# 51-2001-01-12_04_Power_Module_Schematic.net
KiCad netlist of a schematic drawn in Altium Designer
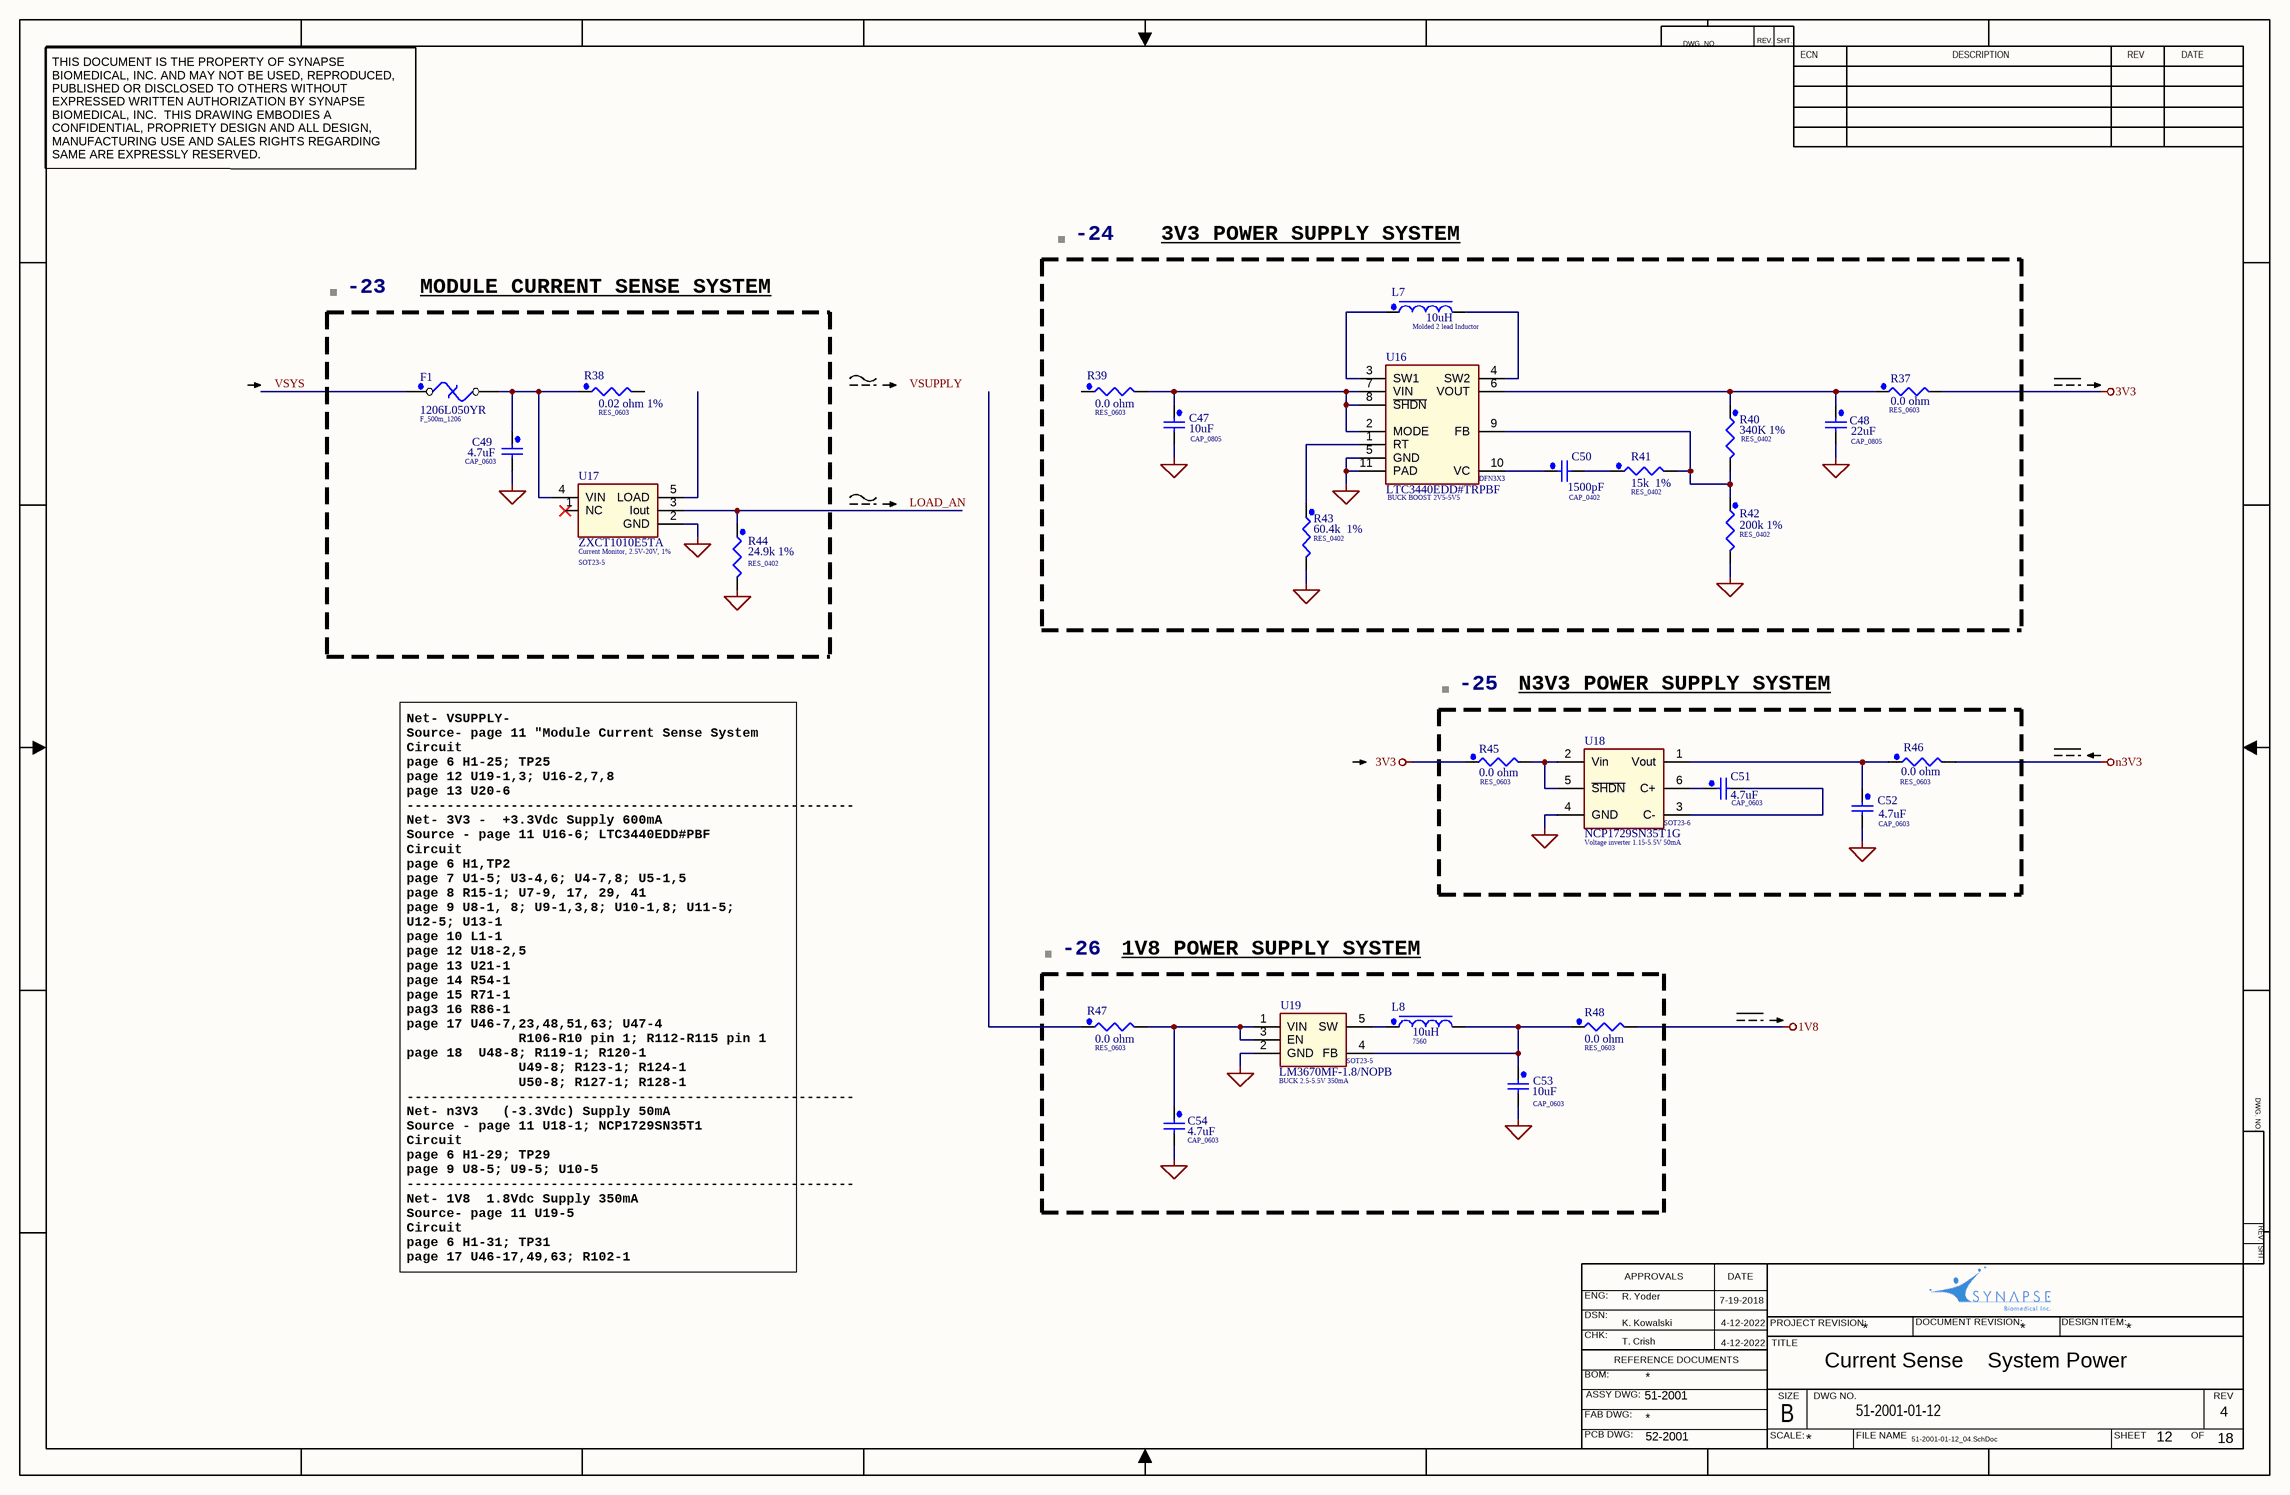
[diagram p0: 51-2001-01-12_04 Power Module Schematic.SchDoc]

(export (version "E")
  (design (tool "Eeschema 10.0.6"))
  (components
    (comp (ref "-23")
      (value "BOM_S1")
      (description "BOM item small graphic")
      (fields (field (name "XDESCRIPTION") "MODULE CURRENT SENSE SYSTEM"))
      (libsource (lib "BOM_sym") (part "BOM_S1"))
    )
    (comp (ref "-24")
      (value "BOM_S1")
      (description "BOM item small graphic")
      (fields (field (name "XDESCRIPTION") "3V3 POWER SUPPLY SYSTEM"))
      (libsource (lib "BOM_sym") (part "BOM_S1"))
    )
    (comp (ref "-25")
      (value "BOM_S1")
      (description "BOM item small graphic")
      (fields (field (name "XDESCRIPTION") "N3V3 POWER SUPPLY SYSTEM"))
      (libsource (lib "BOM_sym") (part "BOM_S1"))
    )
    (comp (ref "-26")
      (value "BOM_S1")
      (description "BOM item small graphic")
      (fields (field (name "XDESCRIPTION") "1V8 POWER SUPPLY SYSTEM"))
      (libsource (lib "BOM_sym") (part "BOM_S1"))
    )
    (comp (ref "C47")
      (value "10uF")
      (footprint "CAP_0805")
      (description "10uF, 16V, X5R, 10%, 0805, RoHS")
      (fields
        (field (name "MFR") "Murata Electronics North America")
        (field (name "PACKAGEDESCRIPTION") "CAP_0805")
        (field (name "MPN") "GRM21BR61C106KE15L")
      )
      (libsource (lib "NNPS Integrated Parts") (part "EMK212BJ106KG-T"))
    )
    (comp (ref "C48")
      (value "22uF")
      (footprint "CAP_0805")
      (description "22uF, 6.3V, X5R, 20%, 0805,RoHS")
      (fields
        (field (name "MFR") "Murata Electronics North America")
        (field (name "PACKAGEDESCRIPTION") "CAP_0805")
        (field (name "MPN") "GRM21BR60J226ME39L")
      )
      (libsource (lib "NNPS Integrated Parts") (part "ECJ-2FB0J226M"))
    )
    (comp (ref "C49")
      (value "4.7uF")
      (footprint "CAP_0603")
      (description "4.7uF, 10V, X5R, 10%, 0603, RoHS")
      (fields
        (field (name "MFR") "Murata Electronics North America")
        (field (name "PACKAGEDESCRIPTION") "CAP_0603")
        (field (name "MPN") "GRM185R61A475KE11D")
      )
      (libsource (lib "NNPS Integrated Parts") (part "LMK107BJ475KA-T"))
    )
    (comp (ref "C50")
      (value "1500pF")
      (footprint "CAP_0402")
      (description "1500pF, 50V, X7R, 10%, 0402, RoHS")
      (fields
        (field (name "MFR") "Murata Electronics North America")
        (field (name "PACKAGEDESCRIPTION") "CAP_0402")
        (field (name "MPN") "GRM155R71H152KA01D")
      )
      (libsource (lib "NNPS Integrated Parts") (part "ECJ-0EB1H152K"))
    )
    (comp (ref "C51")
      (value "4.7uF")
      (footprint "CAP_0603")
      (description "4.7uF, 10V, X5R, 10%, 0603, RoHS")
      (fields
        (field (name "MFR") "Murata Electronics North America")
        (field (name "PACKAGEDESCRIPTION") "CAP_0603")
        (field (name "MPN") "GRM185R61A475KE11D")
      )
      (libsource (lib "NNPS Integrated Parts") (part "LMK107BJ475KA-T"))
    )
    (comp (ref "C52")
      (value "4.7uF")
      (footprint "CAP_0603")
      (description "4.7uF, 10V, X5R, 10%, 0603, RoHS")
      (fields
        (field (name "MFR") "Murata Electronics North America")
        (field (name "PACKAGEDESCRIPTION") "CAP_0603")
        (field (name "MPN") "GRM185R61A475KE11D")
      )
      (libsource (lib "NNPS Integrated Parts") (part "LMK107BJ475KA-T"))
    )
    (comp (ref "C53")
      (value "10uF")
      (footprint "CAP_0603")
      (description "10uF, 6.3V, X5R, 0603_20%, RoHS")
      (fields
        (field (name "MFR") "Murata Electronics North America")
        (field (name "PACKAGEDESCRIPTION") "CAP_0603")
        (field (name "MPN") "GRM188R60J106ME47J")
      )
      (libsource (lib "NNPS Integrated Parts") (part "ECJ-1VB0J106M"))
    )
    (comp (ref "C54")
      (value "4.7uF")
      (footprint "CAP_0603")
      (description "4.7uF, 10V, X5R, 10%, 0603, RoHS")
      (fields
        (field (name "MFR") "Murata Electronics North America")
        (field (name "PACKAGEDESCRIPTION") "CAP_0603")
        (field (name "MPN") "GRM185R61A475KE11D")
      )
      (libsource (lib "NNPS Integrated Parts") (part "LMK107BJ475KA-T"))
    )
    (comp (ref "F1")
      (value "F_500m_1206")
      (footprint "FUSE_1206")
      (description "PTC Resettable, 500mA, 0.4 ohm,  6V, 1206, RoHS")
      (fields
        (field (name "MFR") "Littelfuse")
        (field (name "PACKAGEDESCRIPTION") "F_500m_1206")
        (field (name "MPN") "1206L050YR")
      )
      (libsource (lib "NNPS Integrated Parts") (part "1206L050YR"))
    )
    (comp (ref "L7")
      (value "10uH")
      (footprint "IND-P1166NL")
      (description "10uH, 1.6A, 20%, 3030, RoHS")
      (fields
        (field (name "MFR") "Pulse")
        (field (name "PACKAGEDESCRIPTION") "Molded 2 lead Inductor")
        (field (name "MPN") "P1166.103T")
      )
      (libsource (lib "NNPS Integrated Parts") (part "P1166.103T"))
    )
    (comp (ref "L8")
      (value "10uH")
      (footprint "IND-ELL-6RH")
      (description "10uH, 1.1A, 2626, 20%, RoHS")
      (fields
        (field (name "MFR") "Panasonic")
        (field (name "PACKAGEDESCRIPTION") "7560")
        (field (name "MPN") "ELL6RH100M")
      )
      (libsource (lib "NNPS Integrated Parts") (part "ELL6RH100M"))
    )
    (comp (ref "R37")
      (value "0.0 ohm")
      (footprint "RES_0603")
      (description "0.0 ohm, 1/16W, 0603, RoHS")
      (fields
        (field (name "MFR") "Vishay Dale")
        (field (name "PACKAGEDESCRIPTION") "RES_0603")
        (field (name "MPN") "CRCW06030000Z0EA")
      )
      (libsource (lib "NNPS Integrated Parts") (part "MCR03ERTJ000"))
    )
    (comp (ref "R38")
      (value "0.02 ohm 1%")
      (footprint "RES_0603")
      (description "0.02 ohm, 1%, 1/10W, 0603, RoHS")
      (fields
        (field (name "MFR") "Vishay Dale")
        (field (name "PACKAGEDESCRIPTION") "RES_0603")
        (field (name "MPN") "WSL0603R0200FEA")
      )
      (libsource (lib "NNPS Integrated Parts") (part "WSL0603R0200FEA"))
    )
    (comp (ref "R39")
      (value "0.0 ohm")
      (footprint "RES_0603")
      (description "0.0 ohm, 1/16W, 0603, RoHS")
      (fields
        (field (name "MFR") "Vishay Dale")
        (field (name "PACKAGEDESCRIPTION") "RES_0603")
        (field (name "MPN") "CRCW06030000Z0EA")
      )
      (libsource (lib "NNPS Integrated Parts") (part "MCR03ERTJ000"))
    )
    (comp (ref "R40")
      (value "340K 1%")
      (footprint "RES_0402")
      (description "340k ohm, 1%, 1/16W, 0402, RoHS")
      (fields
        (field (name "MFR") "Vishay Dale")
        (field (name "PACKAGEDESCRIPTION") "RES_0402")
        (field (name "MPN") "CRCW0402340KFKED")
      )
      (libsource (lib "NNPS Integrated Parts") (part "CRCW0402340KFKED"))
    )
    (comp (ref "R41")
      (value "15k  1%")
      (footprint "RES_0402")
      (description "15.0k ohm, 1%, 1/16W, smd, 0402, RoHS")
      (fields
        (field (name "MFR") "Vishay Dale")
        (field (name "PACKAGEDESCRIPTION") "RES_0402")
        (field (name "MPN") "CRCW040215K0FKED")
      )
      (libsource (lib "NNPS Integrated Parts") (part "MCR01MZPF1502"))
    )
    (comp (ref "R42")
      (value "200k 1%")
      (footprint "RES_0402")
      (description "200k ohm, 1%, 1/16W, 0402, RoHS")
      (fields
        (field (name "MFR") "Vishay Dale")
        (field (name "PACKAGEDESCRIPTION") "RES_0402")
        (field (name "MPN") "CRCW0402200KFKED")
      )
      (libsource (lib "NNPS Integrated Parts") (part "MCR01MZPF2003"))
    )
    (comp (ref "R43")
      (value "60.4k  1%")
      (footprint "RES_0402")
      (description "60.4k ohm, 1%, 1/16W, 0402, RoHS")
      (fields
        (field (name "MFR") "Vishay Dale")
        (field (name "PACKAGEDESCRIPTION") "RES_0402")
        (field (name "MPN") "CRCW040260K4FKED")
      )
      (libsource (lib "NNPS Integrated Parts") (part "MCR01MZPF6042"))
    )
    (comp (ref "R44")
      (value "24.9k 1%")
      (footprint "RES_0402")
      (description "24.9k ohm, 1%, 1/16W, 0402, RoHS")
      (fields
        (field (name "MFR") "Vishay Dale")
        (field (name "PACKAGEDESCRIPTION") "RES_0402")
        (field (name "MPN") "CRCW040224K9FKED")
      )
      (libsource (lib "NNPS Integrated Parts") (part "MCR01MZPF2492"))
    )
    (comp (ref "R45")
      (value "0.0 ohm")
      (footprint "RES_0603")
      (description "0.0 ohm, 1/16W, 0603, RoHS")
      (fields
        (field (name "MFR") "Vishay Dale")
        (field (name "PACKAGEDESCRIPTION") "RES_0603")
        (field (name "MPN") "CRCW06030000Z0EA")
      )
      (libsource (lib "NNPS Integrated Parts") (part "MCR03ERTJ000"))
    )
    (comp (ref "R46")
      (value "0.0 ohm")
      (footprint "RES_0603")
      (description "0.0 ohm, 1/16W, 0603, RoHS")
      (fields
        (field (name "MFR") "Vishay Dale")
        (field (name "PACKAGEDESCRIPTION") "RES_0603")
        (field (name "MPN") "CRCW06030000Z0EA")
      )
      (libsource (lib "NNPS Integrated Parts") (part "MCR03ERTJ000"))
    )
    (comp (ref "R47")
      (value "0.0 ohm")
      (footprint "RES_0603")
      (description "0.0 ohm, 1/16W, 0603, RoHS")
      (fields
        (field (name "MFR") "Vishay Dale")
        (field (name "PACKAGEDESCRIPTION") "RES_0603")
        (field (name "MPN") "CRCW06030000Z0EA")
      )
      (libsource (lib "NNPS Integrated Parts") (part "MCR03ERTJ000"))
    )
    (comp (ref "R48")
      (value "0.0 ohm")
      (footprint "RES_0603")
      (description "0.0 ohm, 1/16W, 0603, RoHS")
      (fields
        (field (name "MFR") "Vishay Dale")
        (field (name "PACKAGEDESCRIPTION") "RES_0603")
        (field (name "MPN") "CRCW06030000Z0EA")
      )
      (libsource (lib "NNPS Integrated Parts") (part "MCR03ERTJ000"))
    )
    (comp (ref "U16")
      (value "BUCK BOOST 2V5-5V5")
      (footprint "DFN10")
      (description "Buck Boost DC/DC, 600mA, DFN, RoHS")
      (fields
        (field (name "MFR") "Linear Technology")
        (field (name "PACKAGEDESCRIPTION") "DFN3X3")
        (field (name "MPN") "LTC3440EDD#TRPBF")
      )
      (libsource (lib "NNPS Integrated Parts") (part "LTC3440EDD"))
    )
    (comp (ref "U17")
      (value "Current Monitor, 2.5V-20V, 1%")
      (footprint "SOT23-5")
      (description "Current Monitor, 2.5V-20V, 1%, RoHS")
      (fields
        (field (name "MFR") "Diodes Incorporated")
        (field (name "PACKAGEDESCRIPTION") "SOT23-5")
        (field (name "MPN") "ZXCT1010E5TA")
      )
      (libsource (lib "NNPS Integrated Parts") (part "ZXCT1010E5TA"))
    )
    (comp (ref "U18")
      (value "Voltage inverter 1.15-5.5V 50mA")
      (footprint "SOT23-6")
      (description "Voltage inverter, 1.15-5.5V, 50mA, SOT23-6, RoHS")
      (fields
        (field (name "MFR") "ON Semiconductor")
        (field (name "PACKAGEDESCRIPTION") "SOT23-6")
        (field (name "MPN") "NCP1729SN35T1G")
      )
      (libsource (lib "NNPS Integrated Parts") (part "NCP1729SN35T1"))
    )
    (comp (ref "U19")
      (value "BUCK 2.5-5.5V 350mA")
      (footprint "SOT23-5")
      (description "Buck Boost, DC/DC, 350mA, SOT23-5, RoHS")
      (fields
        (field (name "MFR") "Texas Instruments")
        (field (name "PACKAGEDESCRIPTION") "SOT23-5")
        (field (name "MPN") "LM3670MF-1.8/NOPB")
      )
      (libsource (lib "NNPS Integrated Parts") (part "LM3670MF-1.8"))
    )
  )
  (nets
    (net (code "1") (name "/LOAD_AN") (class "Default")
      (node (ref "R44") (pin "1") (pinfunction "1_1") (pintype "passive"))
      (node (ref "U17") (pin "3") (pinfunction "Iout_3") (pintype "passive"))
    )
    (net (code "3") (name "/VSYS") (class "Default")
      (node (ref "F1") (pin "1") (pinfunction "1_1") (pintype "passive"))
    )
    (net (code "4") (name "1V8") (class "Default")
      (node (ref "R48") (pin "2") (pinfunction "2_2") (pintype "passive"))
    )
    (net (code "5") (name "3V3") (class "Default")
      (node (ref "R37") (pin "2") (pinfunction "2_2") (pintype "passive"))
      (node (ref "R45") (pin "1") (pinfunction "1_1") (pintype "passive"))
    )
    (net (code "6") (name "GND") (class "Default")
      (node (ref "C47") (pin "2") (pinfunction "2_2") (pintype "passive"))
      (node (ref "C48") (pin "2") (pinfunction "2_2") (pintype "passive"))
      (node (ref "C49") (pin "2") (pinfunction "2_2") (pintype "passive"))
      (node (ref "C52") (pin "2") (pinfunction "2_2") (pintype "passive"))
      (node (ref "C53") (pin "2") (pinfunction "2_2") (pintype "passive"))
      (node (ref "C54") (pin "2") (pinfunction "2_2") (pintype "passive"))
      (node (ref "R42") (pin "2") (pinfunction "2_2") (pintype "passive"))
      (node (ref "R43") (pin "2") (pinfunction "2_2") (pintype "passive"))
      (node (ref "R44") (pin "2") (pinfunction "2_2") (pintype "passive"))
      (node (ref "U16") (pin "11") (pinfunction "PAD_11") (pintype "passive"))
      (node (ref "U16") (pin "5") (pinfunction "GND_5") (pintype "passive"))
      (node (ref "U17") (pin "2") (pinfunction "GND_2") (pintype "power_in"))
      (node (ref "U18") (pin "4") (pinfunction "GND_4") (pintype "passive"))
      (node (ref "U19") (pin "2") (pinfunction "GND_2") (pintype "passive"))
    )
    (net (code "7") (name "Net-(C50-Pad2)") (class "Default")
      (node (ref "C50") (pin "2") (pinfunction "2_2") (pintype "passive"))
      (node (ref "R41") (pin "1") (pinfunction "1_1") (pintype "passive"))
    )
    (net (code "8") (name "Net-(U16-FB)") (class "Default")
      (node (ref "R40") (pin "2") (pinfunction "2_2") (pintype "passive"))
      (node (ref "R41") (pin "2") (pinfunction "2_2") (pintype "passive"))
      (node (ref "R42") (pin "1") (pinfunction "1_1") (pintype "passive"))
      (node (ref "U16") (pin "9") (pinfunction "FB_9") (pintype "passive"))
    )
    (net (code "9") (name "Net-(U16-MODE)") (class "Default")
      (node (ref "C47") (pin "1") (pinfunction "1_1") (pintype "passive"))
      (node (ref "R39") (pin "2") (pinfunction "2_2") (pintype "passive"))
      (node (ref "U16") (pin "2") (pinfunction "MODE_2") (pintype "passive"))
      (node (ref "U16") (pin "7") (pinfunction "VIN_7") (pintype "passive"))
      (node (ref "U16") (pin "8") (pinfunction "SHDN_8") (pintype "passive"))
    )
    (net (code "10") (name "Net-(U16-RT)") (class "Default")
      (node (ref "R43") (pin "1") (pinfunction "1_1") (pintype "passive"))
      (node (ref "U16") (pin "1") (pinfunction "RT_1") (pintype "passive"))
    )
    (net (code "11") (name "Net-(U16-SW1)") (class "Default")
      (node (ref "L7") (pin "1") (pinfunction "1_1") (pintype "passive"))
      (node (ref "U16") (pin "3") (pinfunction "SW1_3") (pintype "passive"))
    )
    (net (code "12") (name "Net-(U16-SW2)") (class "Default")
      (node (ref "L7") (pin "2") (pinfunction "2_2") (pintype "passive"))
      (node (ref "U16") (pin "4") (pinfunction "SW2_4") (pintype "passive"))
    )
    (net (code "13") (name "Net-(U16-VC)") (class "Default")
      (node (ref "C50") (pin "1") (pinfunction "1_1") (pintype "passive"))
      (node (ref "U16") (pin "10") (pinfunction "VC_10") (pintype "passive"))
    )
    (net (code "14") (name "Net-(U16-VOUT)") (class "Default")
      (node (ref "C48") (pin "1") (pinfunction "1_1") (pintype "passive"))
      (node (ref "R37") (pin "1") (pinfunction "1_1") (pintype "passive"))
      (node (ref "R40") (pin "1") (pinfunction "1_1") (pintype "passive"))
      (node (ref "U16") (pin "6") (pinfunction "VOUT_6") (pintype "passive"))
    )
    (net (code "15") (name "Net-(U17-VIN)") (class "Default")
      (node (ref "C49") (pin "1") (pinfunction "1_1") (pintype "passive"))
      (node (ref "F1") (pin "2") (pinfunction "2_2") (pintype "passive"))
      (node (ref "R38") (pin "1") (pinfunction "1_1") (pintype "passive"))
      (node (ref "U17") (pin "4") (pinfunction "VIN_4") (pintype "power_in"))
    )
    (net (code "16") (name "Net-(U18-C+)") (class "Default")
      (node (ref "C51") (pin "1") (pinfunction "1_1") (pintype "passive"))
      (node (ref "U18") (pin "6") (pinfunction "C+_6") (pintype "passive"))
    )
    (net (code "17") (name "Net-(U18-C-)") (class "Default")
      (node (ref "C51") (pin "2") (pinfunction "2_2") (pintype "passive"))
      (node (ref "U18") (pin "3") (pinfunction "C-_3") (pintype "passive"))
    )
    (net (code "18") (name "Net-(U18-SHDN)") (class "Default")
      (node (ref "R45") (pin "2") (pinfunction "2_2") (pintype "passive"))
      (node (ref "U18") (pin "2") (pinfunction "Vin_2") (pintype "passive"))
      (node (ref "U18") (pin "5") (pinfunction "SHDN_5") (pintype "passive"))
    )
    (net (code "19") (name "Net-(U18-Vout)") (class "Default")
      (node (ref "C52") (pin "1") (pinfunction "1_1") (pintype "passive"))
      (node (ref "R46") (pin "1") (pinfunction "1_1") (pintype "passive"))
      (node (ref "U18") (pin "1") (pinfunction "Vout_1") (pintype "passive"))
    )
    (net (code "20") (name "Net-(U19-EN)") (class "Default")
      (node (ref "C54") (pin "1") (pinfunction "1_1") (pintype "passive"))
      (node (ref "R47") (pin "2") (pinfunction "2_2") (pintype "passive"))
      (node (ref "U19") (pin "1") (pinfunction "VIN_1") (pintype "passive"))
      (node (ref "U19") (pin "3") (pinfunction "EN_3") (pintype "passive"))
    )
    (net (code "21") (name "Net-(U19-FB)") (class "Default")
      (node (ref "C53") (pin "1") (pinfunction "1_1") (pintype "passive"))
      (node (ref "L8") (pin "2") (pinfunction "2_2") (pintype "passive"))
      (node (ref "R48") (pin "1") (pinfunction "1_1") (pintype "passive"))
      (node (ref "U19") (pin "4") (pinfunction "FB_4") (pintype "passive"))
    )
    (net (code "22") (name "Net-(U19-SW)") (class "Default")
      (node (ref "L8") (pin "1") (pinfunction "1_1") (pintype "passive"))
      (node (ref "U19") (pin "5") (pinfunction "SW_5") (pintype "passive"))
    )
    (net (code "23") (name "n3V3") (class "Default")
      (node (ref "R46") (pin "2") (pinfunction "2_2") (pintype "passive"))
    )
    (net (code "24") (name "unconnected-(R38-Pad2)") (class "Default")
      (node (ref "R38") (pin "2") (pinfunction "2_2") (pintype "passive"))
    )
    (net (code "25") (name "unconnected-(R39-Pad1)") (class "Default")
      (node (ref "R39") (pin "1") (pinfunction "1_1") (pintype "passive"))
    )
    (net (code "26") (name "unconnected-(R47-Pad1)") (class "Default")
      (node (ref "R47") (pin "1") (pinfunction "1_1") (pintype "passive"))
    )
    (net (code "27") (name "unconnected-(U17-LOAD-Pad5)") (class "Default")
      (node (ref "U17") (pin "5") (pinfunction "LOAD_5") (pintype "passive"))
    )
    (net (code "28") (name "unconnected-(U17-NC-Pad1)") (class "Default")
      (node (ref "U17") (pin "1") (pinfunction "NC_1") (pintype "tri_state+no_connect"))
    )
  )
)
